# IR_PAIR.net
KiCad netlist of a schematic drawn in Altium Designer
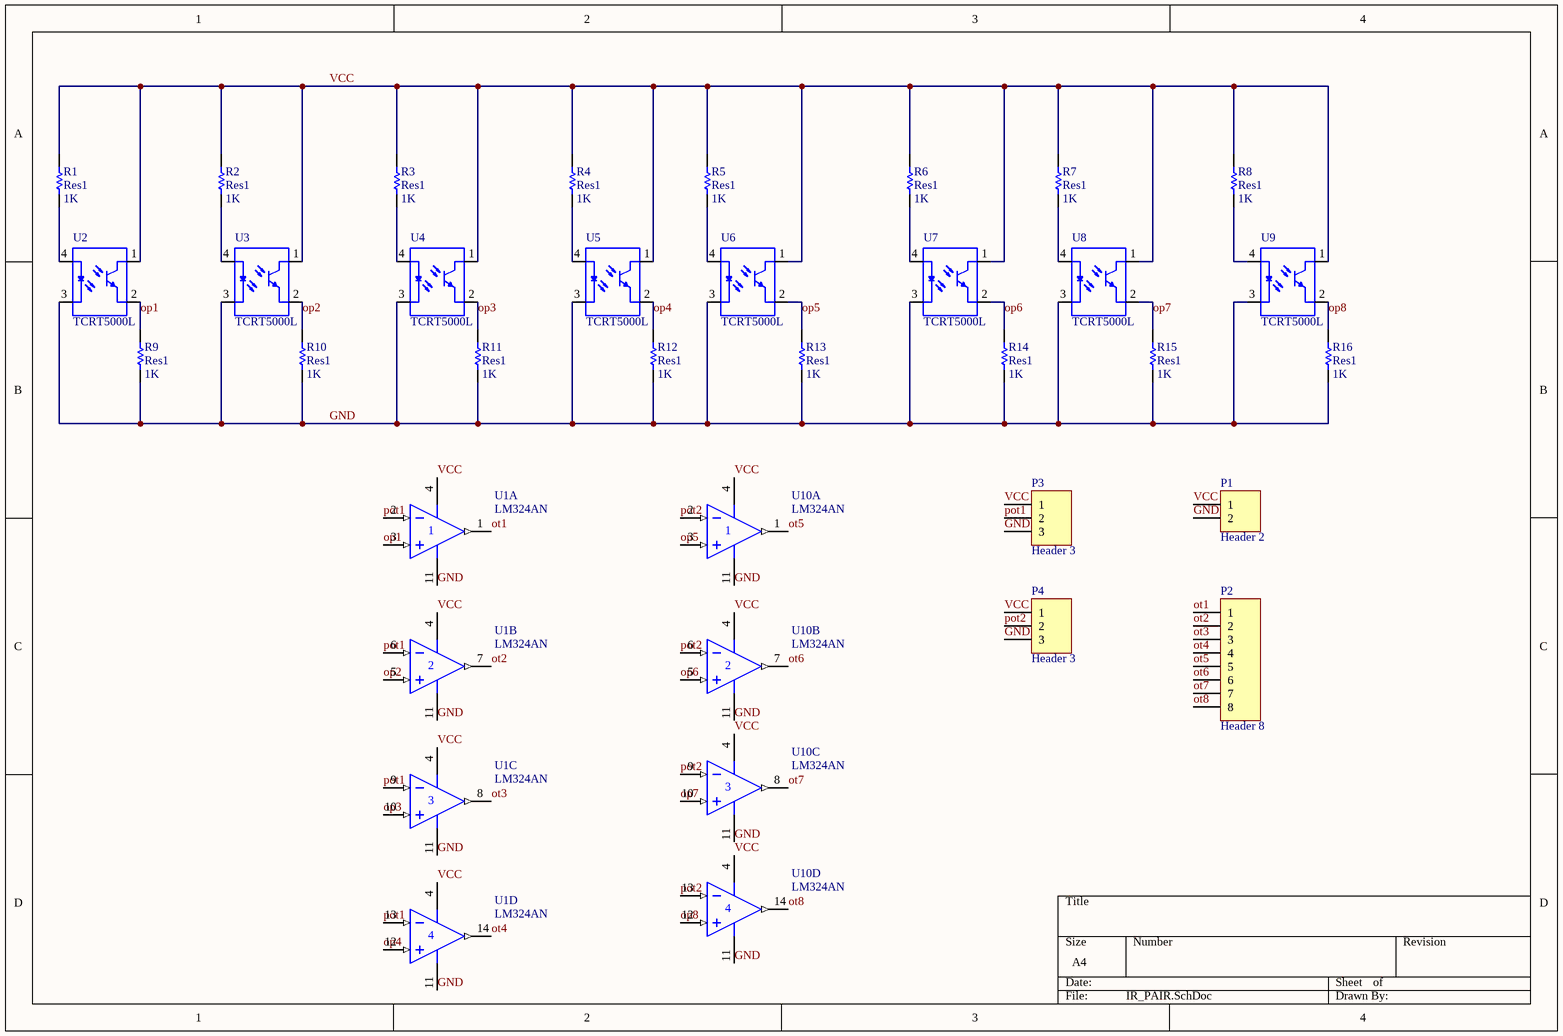
[diagram p0: IR_PAIR.SchDoc]

(export (version "E")
  (design (tool "Eeschema 10.0.6"))
  (components
    (comp (ref "P1")
      (value "Header 2")
      (footprint "HDR1X2")
      (description "Header, 2-Pin")
      (fields (field (name "PUBLISHER") "Altium Limited"))
      (libsource (lib "Miscellaneous Connectors") (part "Header 2"))
    )
    (comp (ref "P2")
      (value "Header 8")
      (footprint "HDR1X8")
      (description "Header, 8-Pin")
      (fields (field (name "PUBLISHER") "Altium Limited"))
      (libsource (lib "Miscellaneous Connectors") (part "Header 8"))
    )
    (comp (ref "P3")
      (value "Header 3")
      (footprint "HDR1X3")
      (description "Header, 3-Pin")
      (fields (field (name "PUBLISHER") "Altium Limited"))
      (libsource (lib "Miscellaneous Connectors") (part "Header 3"))
    )
    (comp (ref "P4")
      (value "Header 3")
      (footprint "HDR1X3")
      (description "Header, 3-Pin")
      (fields (field (name "PUBLISHER") "Altium Limited"))
      (libsource (lib "Miscellaneous Connectors") (part "Header 3"))
    )
    (comp (ref "R1")
      (value "Res1")
      (footprint "AXIAL-0.3")
      (description "Resistor")
      (fields (field (name "ALTIUM_VALUE") "1K") (field (name "PUBLISHER") "Altium Limited"))
      (libsource (lib "Miscellaneous Devices") (part "Res1"))
    )
    (comp (ref "R2")
      (value "Res1")
      (footprint "AXIAL-0.3")
      (description "Resistor")
      (fields (field (name "ALTIUM_VALUE") "1K") (field (name "PUBLISHER") "Altium Limited"))
      (libsource (lib "Miscellaneous Devices") (part "Res1"))
    )
    (comp (ref "R3")
      (value "Res1")
      (footprint "AXIAL-0.3")
      (description "Resistor")
      (fields (field (name "ALTIUM_VALUE") "1K") (field (name "PUBLISHER") "Altium Limited"))
      (libsource (lib "Miscellaneous Devices") (part "Res1"))
    )
    (comp (ref "R4")
      (value "Res1")
      (footprint "AXIAL-0.3")
      (description "Resistor")
      (fields (field (name "ALTIUM_VALUE") "1K") (field (name "PUBLISHER") "Altium Limited"))
      (libsource (lib "Miscellaneous Devices") (part "Res1"))
    )
    (comp (ref "R5")
      (value "Res1")
      (footprint "AXIAL-0.3")
      (description "Resistor")
      (fields (field (name "ALTIUM_VALUE") "1K") (field (name "PUBLISHER") "Altium Limited"))
      (libsource (lib "Miscellaneous Devices") (part "Res1"))
    )
    (comp (ref "R6")
      (value "Res1")
      (footprint "AXIAL-0.3")
      (description "Resistor")
      (fields (field (name "ALTIUM_VALUE") "1K") (field (name "PUBLISHER") "Altium Limited"))
      (libsource (lib "Miscellaneous Devices") (part "Res1"))
    )
    (comp (ref "R7")
      (value "Res1")
      (footprint "AXIAL-0.3")
      (description "Resistor")
      (fields (field (name "ALTIUM_VALUE") "1K") (field (name "PUBLISHER") "Altium Limited"))
      (libsource (lib "Miscellaneous Devices") (part "Res1"))
    )
    (comp (ref "R8")
      (value "Res1")
      (footprint "AXIAL-0.3")
      (description "Resistor")
      (fields (field (name "ALTIUM_VALUE") "1K") (field (name "PUBLISHER") "Altium Limited"))
      (libsource (lib "Miscellaneous Devices") (part "Res1"))
    )
    (comp (ref "R9")
      (value "Res1")
      (footprint "AXIAL-0.3")
      (description "Resistor")
      (fields (field (name "ALTIUM_VALUE") "1K") (field (name "PUBLISHER") "Altium Limited"))
      (libsource (lib "Miscellaneous Devices") (part "Res1"))
    )
    (comp (ref "R10")
      (value "Res1")
      (footprint "AXIAL-0.3")
      (description "Resistor")
      (fields (field (name "ALTIUM_VALUE") "1K") (field (name "PUBLISHER") "Altium Limited"))
      (libsource (lib "Miscellaneous Devices") (part "Res1"))
    )
    (comp (ref "R11")
      (value "Res1")
      (footprint "AXIAL-0.3")
      (description "Resistor")
      (fields (field (name "ALTIUM_VALUE") "1K") (field (name "PUBLISHER") "Altium Limited"))
      (libsource (lib "Miscellaneous Devices") (part "Res1"))
    )
    (comp (ref "R12")
      (value "Res1")
      (footprint "AXIAL-0.3")
      (description "Resistor")
      (fields (field (name "ALTIUM_VALUE") "1K") (field (name "PUBLISHER") "Altium Limited"))
      (libsource (lib "Miscellaneous Devices") (part "Res1"))
    )
    (comp (ref "R13")
      (value "Res1")
      (footprint "AXIAL-0.3")
      (description "Resistor")
      (fields (field (name "ALTIUM_VALUE") "1K") (field (name "PUBLISHER") "Altium Limited"))
      (libsource (lib "Miscellaneous Devices") (part "Res1"))
    )
    (comp (ref "R14")
      (value "Res1")
      (footprint "AXIAL-0.3")
      (description "Resistor")
      (fields (field (name "ALTIUM_VALUE") "1K") (field (name "PUBLISHER") "Altium Limited"))
      (libsource (lib "Miscellaneous Devices") (part "Res1"))
    )
    (comp (ref "R15")
      (value "Res1")
      (footprint "AXIAL-0.3")
      (description "Resistor")
      (fields (field (name "ALTIUM_VALUE") "1K") (field (name "PUBLISHER") "Altium Limited"))
      (libsource (lib "Miscellaneous Devices") (part "Res1"))
    )
    (comp (ref "R16")
      (value "Res1")
      (footprint "AXIAL-0.3")
      (description "Resistor")
      (fields (field (name "ALTIUM_VALUE") "1K") (field (name "PUBLISHER") "Altium Limited"))
      (libsource (lib "Miscellaneous Devices") (part "Res1"))
    )
    (comp (ref "U1")
      (value "LM324AN")
      (footprint "N014")
      (description "Quadruple Operational Amplifier")
      (fields (field (name "PUBLISHER") "Altium Limited"))
      (libsource (lib "TI Operational Amplifier") (part "LM324AN"))
    )
    (comp (ref "U2")
      (value "TCRT5000L")
      (footprint "XDCR_TCRT5000L")
      (description "TCRT5000 Series 940 nm 100 mA 60 mA Transistor Output Reflective Optical Sensor")
      (fields (field (name "MF") "Vishay Semiconductor"))
      (libsource (lib "TCRT5000L") (part "TCRT5000L"))
    )
    (comp (ref "U3")
      (value "TCRT5000L")
      (footprint "XDCR_TCRT5000L")
      (description "TCRT5000 Series 940 nm 100 mA 60 mA Transistor Output Reflective Optical Sensor")
      (fields (field (name "MF") "Vishay Semiconductor"))
      (libsource (lib "TCRT5000L") (part "TCRT5000L"))
    )
    (comp (ref "U4")
      (value "TCRT5000L")
      (footprint "XDCR_TCRT5000L")
      (description "TCRT5000 Series 940 nm 100 mA 60 mA Transistor Output Reflective Optical Sensor")
      (fields (field (name "MF") "Vishay Semiconductor"))
      (libsource (lib "TCRT5000L") (part "TCRT5000L"))
    )
    (comp (ref "U5")
      (value "TCRT5000L")
      (footprint "XDCR_TCRT5000L")
      (description "TCRT5000 Series 940 nm 100 mA 60 mA Transistor Output Reflective Optical Sensor")
      (fields (field (name "MF") "Vishay Semiconductor"))
      (libsource (lib "TCRT5000L") (part "TCRT5000L"))
    )
    (comp (ref "U6")
      (value "TCRT5000L")
      (footprint "XDCR_TCRT5000L")
      (description "TCRT5000 Series 940 nm 100 mA 60 mA Transistor Output Reflective Optical Sensor")
      (fields (field (name "MF") "Vishay Semiconductor"))
      (libsource (lib "TCRT5000L") (part "TCRT5000L"))
    )
    (comp (ref "U7")
      (value "TCRT5000L")
      (footprint "XDCR_TCRT5000L")
      (description "TCRT5000 Series 940 nm 100 mA 60 mA Transistor Output Reflective Optical Sensor")
      (fields (field (name "MF") "Vishay Semiconductor"))
      (libsource (lib "TCRT5000L") (part "TCRT5000L"))
    )
    (comp (ref "U8")
      (value "TCRT5000L")
      (footprint "XDCR_TCRT5000L")
      (description "TCRT5000 Series 940 nm 100 mA 60 mA Transistor Output Reflective Optical Sensor")
      (fields (field (name "MF") "Vishay Semiconductor"))
      (libsource (lib "TCRT5000L") (part "TCRT5000L"))
    )
    (comp (ref "U9")
      (value "TCRT5000L")
      (footprint "XDCR_TCRT5000L")
      (description "TCRT5000 Series 940 nm 100 mA 60 mA Transistor Output Reflective Optical Sensor")
      (fields (field (name "MF") "Vishay Semiconductor"))
      (libsource (lib "TCRT5000L") (part "TCRT5000L"))
    )
    (comp (ref "U10")
      (value "LM324AN")
      (footprint "N014")
      (description "Quadruple Operational Amplifier")
      (fields (field (name "PUBLISHER") "Altium Limited"))
      (libsource (lib "TI Operational Amplifier") (part "LM324AN"))
    )
  )
  (nets
    (net (code "1") (name "/GND") (class "Default")
      (node (ref "P1") (pin "2") (pinfunction "2_2") (pintype "passive"))
      (node (ref "P3") (pin "3") (pinfunction "3_3") (pintype "passive"))
      (node (ref "P4") (pin "3") (pinfunction "3_3") (pintype "passive"))
      (node (ref "R10") (pin "1") (pinfunction "1_1") (pintype "passive"))
      (node (ref "R11") (pin "1") (pinfunction "1_1") (pintype "passive"))
      (node (ref "R12") (pin "1") (pinfunction "1_1") (pintype "passive"))
      (node (ref "R13") (pin "1") (pinfunction "1_1") (pintype "passive"))
      (node (ref "R14") (pin "1") (pinfunction "1_1") (pintype "passive"))
      (node (ref "R15") (pin "1") (pinfunction "1_1") (pintype "passive"))
      (node (ref "R16") (pin "1") (pinfunction "1_1") (pintype "passive"))
      (node (ref "R9") (pin "1") (pinfunction "1_1") (pintype "passive"))
      (node (ref "U1") (pin "11") (pinfunction "V-_11") (pintype "power_in"))
      (node (ref "U10") (pin "11") (pinfunction "V-_11") (pintype "power_in"))
      (node (ref "U2") (pin "3") (pinfunction "C_3") (pintype "passive"))
      (node (ref "U3") (pin "3") (pinfunction "C_3") (pintype "passive"))
      (node (ref "U4") (pin "3") (pinfunction "C_3") (pintype "passive"))
      (node (ref "U5") (pin "3") (pinfunction "C_3") (pintype "passive"))
      (node (ref "U6") (pin "3") (pinfunction "C_3") (pintype "passive"))
      (node (ref "U7") (pin "3") (pinfunction "C_3") (pintype "passive"))
      (node (ref "U8") (pin "3") (pinfunction "C_3") (pintype "passive"))
      (node (ref "U9") (pin "3") (pinfunction "C_3") (pintype "passive"))
    )
    (net (code "2") (name "/VCC") (class "Default")
      (node (ref "P1") (pin "1") (pinfunction "1_1") (pintype "passive"))
      (node (ref "P3") (pin "1") (pinfunction "1_1") (pintype "passive"))
      (node (ref "P4") (pin "1") (pinfunction "1_1") (pintype "passive"))
      (node (ref "R1") (pin "2") (pinfunction "2_2") (pintype "passive"))
      (node (ref "R2") (pin "2") (pinfunction "2_2") (pintype "passive"))
      (node (ref "R3") (pin "2") (pinfunction "2_2") (pintype "passive"))
      (node (ref "R4") (pin "2") (pinfunction "2_2") (pintype "passive"))
      (node (ref "R5") (pin "2") (pinfunction "2_2") (pintype "passive"))
      (node (ref "R6") (pin "2") (pinfunction "2_2") (pintype "passive"))
      (node (ref "R7") (pin "2") (pinfunction "2_2") (pintype "passive"))
      (node (ref "R8") (pin "2") (pinfunction "2_2") (pintype "passive"))
      (node (ref "U1") (pin "4") (pinfunction "V+_4") (pintype "power_in"))
      (node (ref "U10") (pin "4") (pinfunction "V+_4") (pintype "power_in"))
      (node (ref "U2") (pin "1") (pinfunction "CO_1") (pintype "passive"))
      (node (ref "U3") (pin "1") (pinfunction "CO_1") (pintype "passive"))
      (node (ref "U4") (pin "1") (pinfunction "CO_1") (pintype "passive"))
      (node (ref "U5") (pin "1") (pinfunction "CO_1") (pintype "passive"))
      (node (ref "U6") (pin "1") (pinfunction "CO_1") (pintype "passive"))
      (node (ref "U7") (pin "1") (pinfunction "CO_1") (pintype "passive"))
      (node (ref "U8") (pin "1") (pinfunction "CO_1") (pintype "passive"))
      (node (ref "U9") (pin "1") (pinfunction "CO_1") (pintype "passive"))
    )
    (net (code "3") (name "/op1") (class "Default")
      (node (ref "R9") (pin "2") (pinfunction "2_2") (pintype "passive"))
      (node (ref "U1") (pin "3") (pinfunction "IN+_3") (pintype "input"))
      (node (ref "U2") (pin "2") (pinfunction "E_2") (pintype "passive"))
    )
    (net (code "4") (name "/op2") (class "Default")
      (node (ref "R10") (pin "2") (pinfunction "2_2") (pintype "passive"))
      (node (ref "U1") (pin "5") (pinfunction "IN+_5") (pintype "input"))
      (node (ref "U3") (pin "2") (pinfunction "E_2") (pintype "passive"))
    )
    (net (code "5") (name "/op3") (class "Default")
      (node (ref "R11") (pin "2") (pinfunction "2_2") (pintype "passive"))
      (node (ref "U1") (pin "10") (pinfunction "IN+_10") (pintype "input"))
      (node (ref "U4") (pin "2") (pinfunction "E_2") (pintype "passive"))
    )
    (net (code "6") (name "/op4") (class "Default")
      (node (ref "R12") (pin "2") (pinfunction "2_2") (pintype "passive"))
      (node (ref "U1") (pin "12") (pinfunction "IN+_12") (pintype "input"))
      (node (ref "U5") (pin "2") (pinfunction "E_2") (pintype "passive"))
    )
    (net (code "7") (name "/op5") (class "Default")
      (node (ref "R13") (pin "2") (pinfunction "2_2") (pintype "passive"))
      (node (ref "U10") (pin "3") (pinfunction "IN+_3") (pintype "input"))
      (node (ref "U6") (pin "2") (pinfunction "E_2") (pintype "passive"))
    )
    (net (code "8") (name "/op6") (class "Default")
      (node (ref "R14") (pin "2") (pinfunction "2_2") (pintype "passive"))
      (node (ref "U10") (pin "5") (pinfunction "IN+_5") (pintype "input"))
      (node (ref "U7") (pin "2") (pinfunction "E_2") (pintype "passive"))
    )
    (net (code "9") (name "/op7") (class "Default")
      (node (ref "R15") (pin "2") (pinfunction "2_2") (pintype "passive"))
      (node (ref "U10") (pin "10") (pinfunction "IN+_10") (pintype "input"))
      (node (ref "U8") (pin "2") (pinfunction "E_2") (pintype "passive"))
    )
    (net (code "10") (name "/op8") (class "Default")
      (node (ref "R16") (pin "2") (pinfunction "2_2") (pintype "passive"))
      (node (ref "U10") (pin "12") (pinfunction "IN+_12") (pintype "input"))
      (node (ref "U9") (pin "2") (pinfunction "E_2") (pintype "passive"))
    )
    (net (code "11") (name "/ot1") (class "Default")
      (node (ref "P2") (pin "1") (pinfunction "1_1") (pintype "passive"))
      (node (ref "U1") (pin "1") (pinfunction "OUT_1") (pintype "output"))
    )
    (net (code "12") (name "/ot2") (class "Default")
      (node (ref "P2") (pin "2") (pinfunction "2_2") (pintype "passive"))
      (node (ref "U1") (pin "7") (pinfunction "OUT_7") (pintype "output"))
    )
    (net (code "13") (name "/ot3") (class "Default")
      (node (ref "P2") (pin "3") (pinfunction "3_3") (pintype "passive"))
      (node (ref "U1") (pin "8") (pinfunction "OUT_8") (pintype "output"))
    )
    (net (code "14") (name "/ot4") (class "Default")
      (node (ref "P2") (pin "4") (pinfunction "4_4") (pintype "passive"))
      (node (ref "U1") (pin "14") (pinfunction "OUT_14") (pintype "output"))
    )
    (net (code "15") (name "/ot5") (class "Default")
      (node (ref "P2") (pin "5") (pinfunction "5_5") (pintype "passive"))
      (node (ref "U10") (pin "1") (pinfunction "OUT_1") (pintype "output"))
    )
    (net (code "16") (name "/ot6") (class "Default")
      (node (ref "P2") (pin "6") (pinfunction "6_6") (pintype "passive"))
      (node (ref "U10") (pin "7") (pinfunction "OUT_7") (pintype "output"))
    )
    (net (code "17") (name "/ot7") (class "Default")
      (node (ref "P2") (pin "7") (pinfunction "7_7") (pintype "passive"))
      (node (ref "U10") (pin "8") (pinfunction "OUT_8") (pintype "output"))
    )
    (net (code "18") (name "/ot8") (class "Default")
      (node (ref "P2") (pin "8") (pinfunction "8_8") (pintype "passive"))
      (node (ref "U10") (pin "14") (pinfunction "OUT_14") (pintype "output"))
    )
    (net (code "19") (name "/pot1") (class "Default")
      (node (ref "P3") (pin "2") (pinfunction "2_2") (pintype "passive"))
      (node (ref "U1") (pin "13") (pinfunction "IN-_13") (pintype "input"))
      (node (ref "U1") (pin "2") (pinfunction "IN-_2") (pintype "input"))
      (node (ref "U1") (pin "6") (pinfunction "IN-_6") (pintype "input"))
      (node (ref "U1") (pin "9") (pinfunction "IN-_9") (pintype "input"))
    )
    (net (code "20") (name "/pot2") (class "Default")
      (node (ref "P4") (pin "2") (pinfunction "2_2") (pintype "passive"))
      (node (ref "U10") (pin "13") (pinfunction "IN-_13") (pintype "input"))
      (node (ref "U10") (pin "2") (pinfunction "IN-_2") (pintype "input"))
      (node (ref "U10") (pin "6") (pinfunction "IN-_6") (pintype "input"))
      (node (ref "U10") (pin "9") (pinfunction "IN-_9") (pintype "input"))
    )
    (net (code "21") (name "Net-(U2-A)") (class "Default")
      (node (ref "R1") (pin "1") (pinfunction "1_1") (pintype "passive"))
      (node (ref "U2") (pin "4") (pinfunction "A_4") (pintype "passive"))
    )
    (net (code "22") (name "Net-(U3-A)") (class "Default")
      (node (ref "R2") (pin "1") (pinfunction "1_1") (pintype "passive"))
      (node (ref "U3") (pin "4") (pinfunction "A_4") (pintype "passive"))
    )
    (net (code "23") (name "Net-(U4-A)") (class "Default")
      (node (ref "R3") (pin "1") (pinfunction "1_1") (pintype "passive"))
      (node (ref "U4") (pin "4") (pinfunction "A_4") (pintype "passive"))
    )
    (net (code "24") (name "Net-(U5-A)") (class "Default")
      (node (ref "R4") (pin "1") (pinfunction "1_1") (pintype "passive"))
      (node (ref "U5") (pin "4") (pinfunction "A_4") (pintype "passive"))
    )
    (net (code "25") (name "Net-(U6-A)") (class "Default")
      (node (ref "R5") (pin "1") (pinfunction "1_1") (pintype "passive"))
      (node (ref "U6") (pin "4") (pinfunction "A_4") (pintype "passive"))
    )
    (net (code "26") (name "Net-(U7-A)") (class "Default")
      (node (ref "R6") (pin "1") (pinfunction "1_1") (pintype "passive"))
      (node (ref "U7") (pin "4") (pinfunction "A_4") (pintype "passive"))
    )
    (net (code "27") (name "Net-(U8-A)") (class "Default")
      (node (ref "R7") (pin "1") (pinfunction "1_1") (pintype "passive"))
      (node (ref "U8") (pin "4") (pinfunction "A_4") (pintype "passive"))
    )
    (net (code "28") (name "Net-(U9-A)") (class "Default")
      (node (ref "R8") (pin "1") (pinfunction "1_1") (pintype "passive"))
      (node (ref "U9") (pin "4") (pinfunction "A_4") (pintype "passive"))
    )
  )
)
